# MySens-easyESP32-011.net
KiCad netlist of a schematic drawn in EAGLE
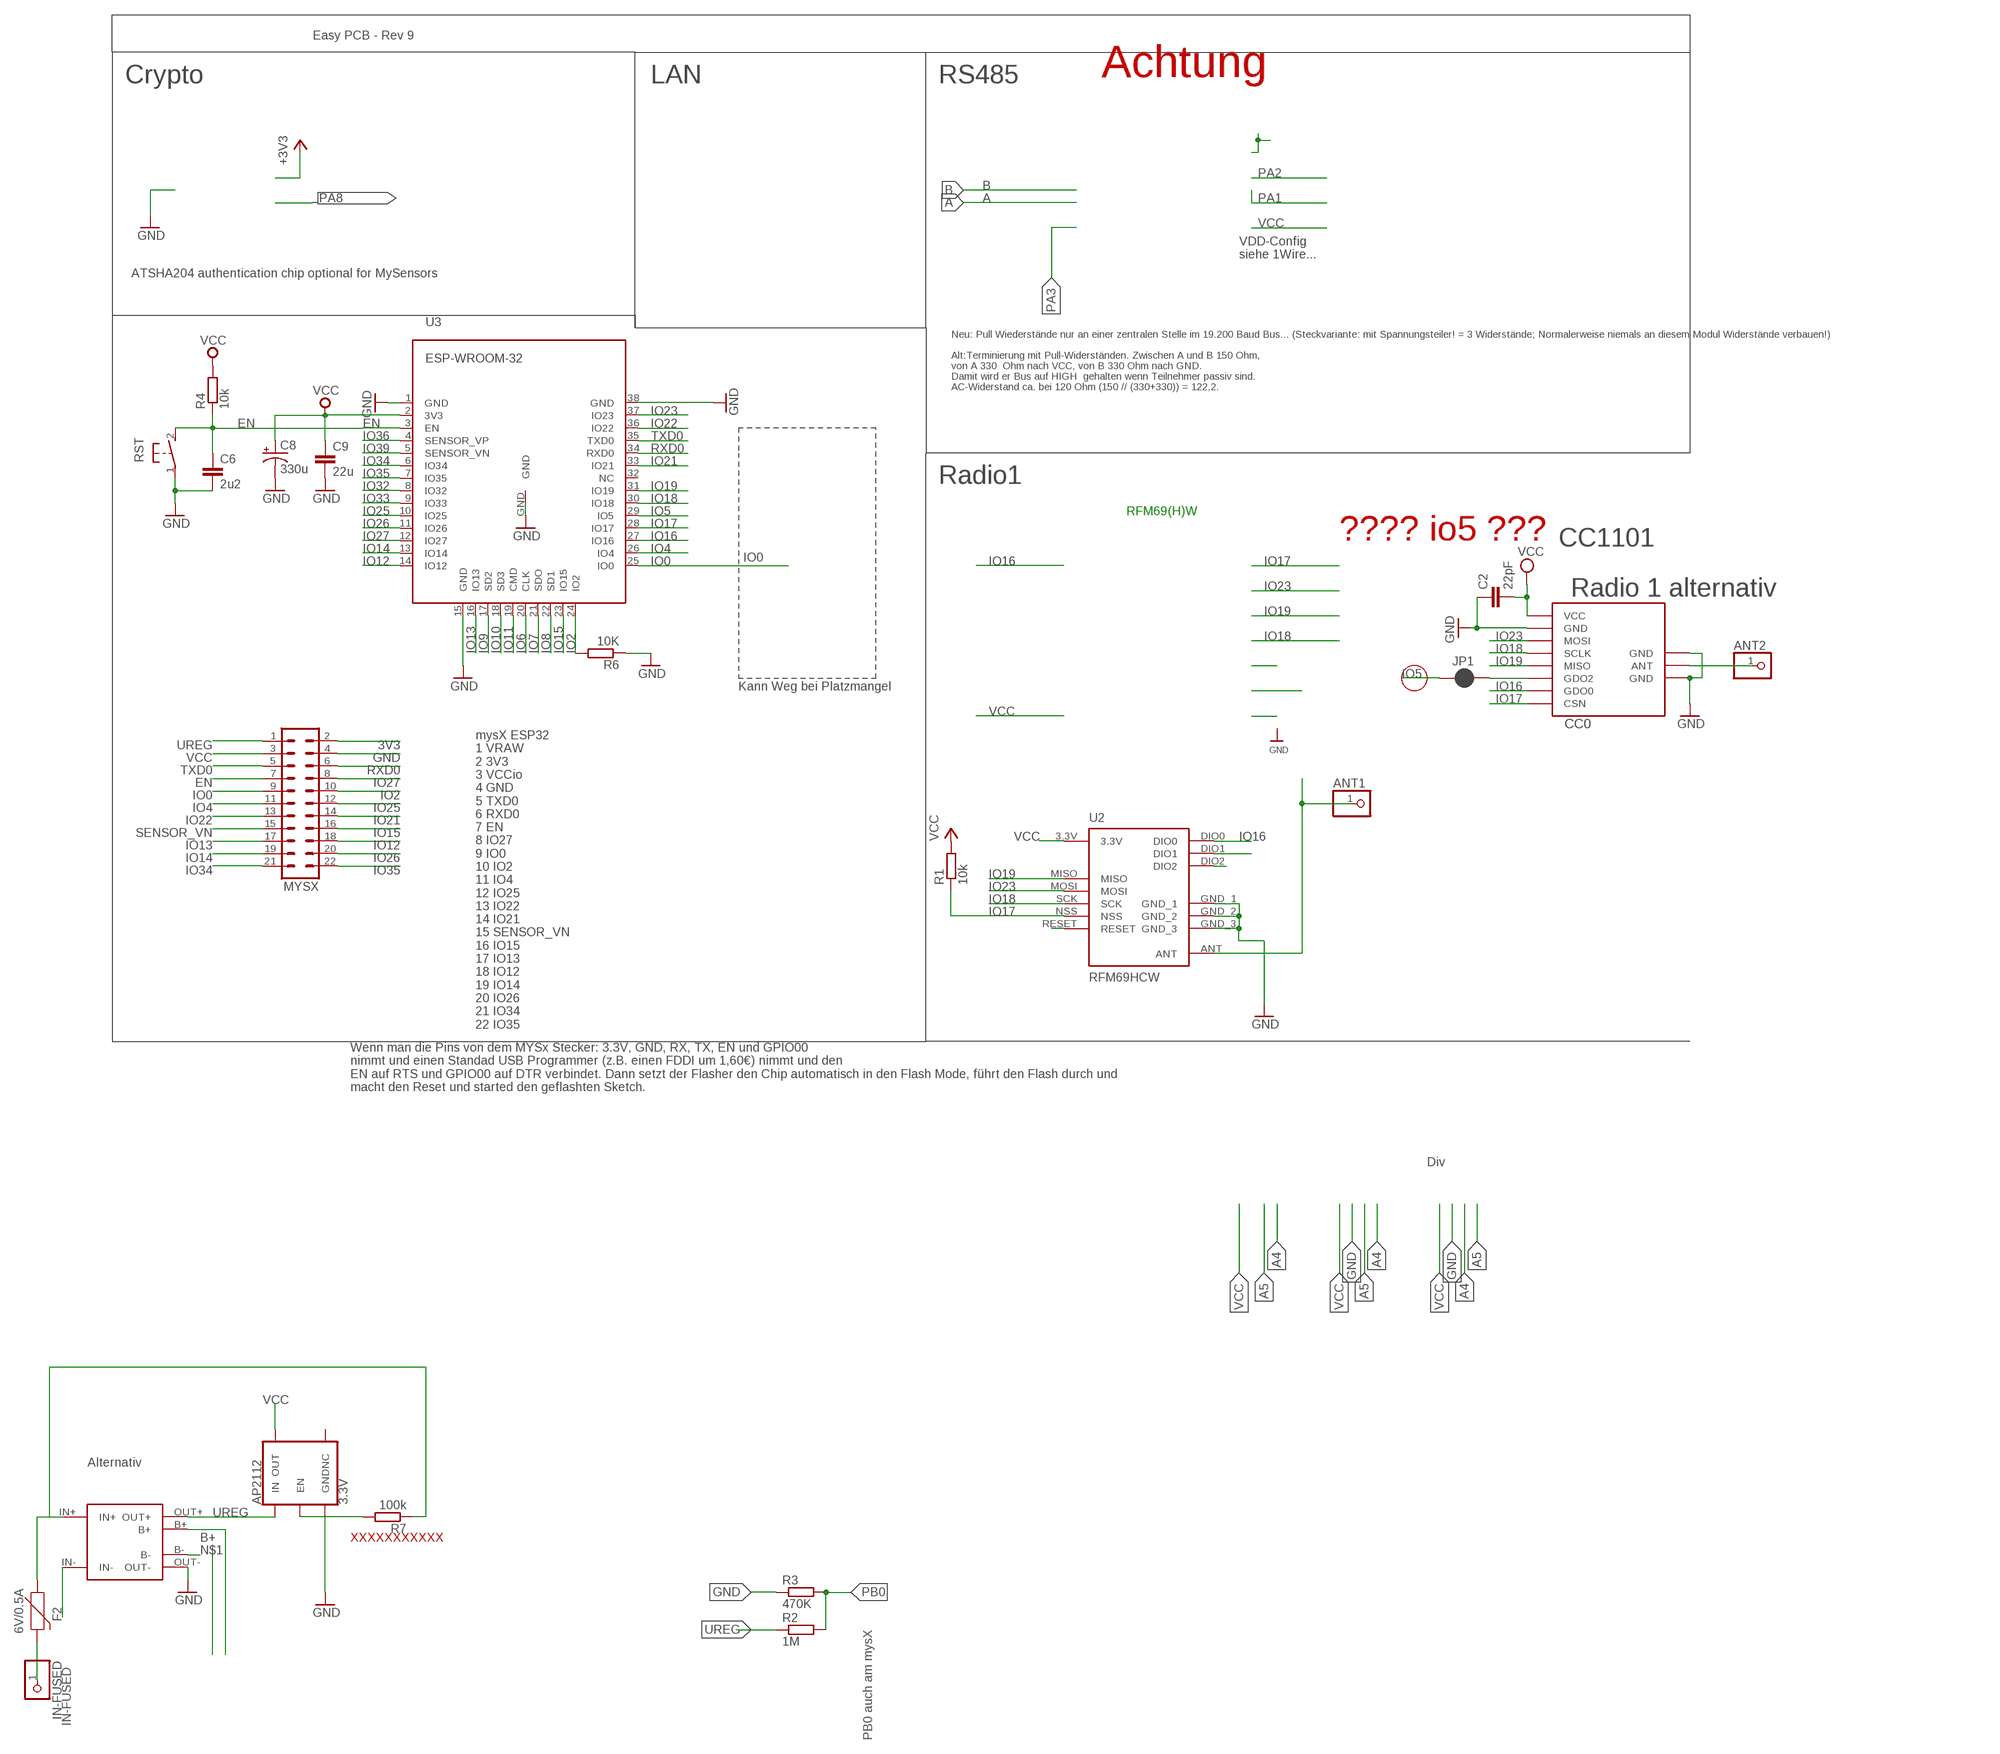
[diagram p0: schematic, sheet 1]

(export (version "E")
  (design (tool "Eeschema 10.0.6"))
  (components
    (comp (ref "ANT1")
      (value "PINHD-1X1")
      (footprint "eagle-import:1X01")
      (libsource (lib "eagle-import") (part "PINHD-1X1"))
    )
    (comp (ref "ANT2")
      (value "PINHD-1X1")
      (footprint "eagle-import:1X01")
      (libsource (lib "eagle-import") (part "PINHD-1X1"))
    )
    (comp (ref "AP2112")
      (value "3.3V")
      (footprint "eagle-import:SOT23-5")
      (libsource (lib "eagle-import") (part "V_REG_AP2112K-3.3V"))
    )
    (comp (ref "C2")
      (value "22pF")
      (footprint "eagle-import:C0805")
      (libsource (lib "eagle-import") (part "C-EUC0805"))
    )
    (comp (ref "C6")
      (value "2u2")
      (footprint "eagle-import:C0805")
      (libsource (lib "eagle-import") (part "rcl@1_C-EUC0805"))
    )
    (comp (ref "C8")
      (value "330u")
      (footprint "eagle-import:VISHAY_C")
      (libsource (lib "eagle-import") (part "CAP_POLSMD"))
    )
    (comp (ref "C9")
      (value "22u")
      (footprint "eagle-import:C0805")
      (libsource (lib "eagle-import") (part "rcl@1_C-EUC0805"))
    )
    (comp (ref "CC0")
      (value "CC1101")
      (footprint "eagle-import:CC1101_MODULE1_SMD")
      (libsource (lib "eagle-import") (part "CC1101_MODULE1SMD"))
    )
    (comp (ref "F2")
      (value "6V/0.5A")
      (footprint "eagle-import:1206")
      (libsource (lib "eagle-import") (part "PPTC_HALF-AMP"))
    )
    (comp (ref "IN-FUSED")
      (value "PINHD-1X1")
      (footprint "eagle-import:1X01")
      (libsource (lib "eagle-import") (part "PINHD-1X1"))
    )
    (comp (ref "JP1")
      (value "JUMPER-SMT_2_NC_PASTE_NO-SILK")
      (footprint "eagle-import:SMT-JUMPER_2_NC_PASTE_NO-SILK")
      (libsource (lib "eagle-import") (part "JUMPER-SMT_2_NC_PASTE_NO-SILK"))
    )
    (comp (ref "MYSX")
      (value "MA11-2")
      (footprint "eagle-import:MA11-2")
      (libsource (lib "eagle-import") (part "MA11-2"))
    )
    (comp (ref "R1")
      (value "10k")
      (footprint "eagle-import:M0805")
      (libsource (lib "eagle-import") (part "R-EU_M0805"))
    )
    (comp (ref "R2")
      (value "1M")
      (footprint "eagle-import:M0805")
      (libsource (lib "eagle-import") (part "R-EU_M0805"))
    )
    (comp (ref "R3")
      (value "470K")
      (footprint "eagle-import:M0805")
      (libsource (lib "eagle-import") (part "R-EU_M0805"))
    )
    (comp (ref "R4")
      (value "10k")
      (footprint "eagle-import:M0805")
      (libsource (lib "eagle-import") (part "rcl@1_R-EU_M0805"))
    )
    (comp (ref "R6")
      (value "10K")
      (footprint "eagle-import:M0805")
      (libsource (lib "eagle-import") (part "R-EU_M0805"))
    )
    (comp (ref "R7")
      (value "100k")
      (footprint "eagle-import:M0805")
      (libsource (lib "eagle-import") (part "R-EU_M0805"))
    )
    (comp (ref "RST")
      (value "DTSM-3")
      (footprint "eagle-import:DTSM-3")
      (libsource (lib "eagle-import") (part "DTSM-3"))
    )
    (comp (ref "TP4056")
      (value "TP4056-MODULE")
      (footprint "eagle-import:TP4056-LITHIUM-PROTECTED-MODULE")
      (libsource (lib "eagle-import") (part "TP4056-MODULE"))
    )
    (comp (ref "U2")
      (value "RFM69HCW")
      (footprint "eagle-import:RFM69HCW-XXXS2")
      (libsource (lib "eagle-import") (part "RFM69HCW"))
    )
    (comp (ref "U3")
      (value "ESP-WROOM-32")
      (footprint "eagle-import:ESP-WROOM-32")
      (libsource (lib "eagle-import") (part "ESP-WROOM-32"))
    )
  )
  (nets
    (net (code "2") (name "/3V3") (class "Default")
      (node (ref "MYSX") (pin "2") (pinfunction "2_2") (pintype "passive"))
    )
    (net (code "3") (name "/B+") (class "Default")
      (node (ref "TP4056") (pin "B+") (pinfunction "B+_B+") (pintype "power_in"))
    )
    (net (code "4") (name "/EN") (class "Default")
      (node (ref "C6") (pin "1") (pinfunction "1_1") (pintype "passive"))
      (node (ref "MYSX") (pin "7") (pinfunction "7_7") (pintype "passive"))
      (node (ref "R4") (pin "1") (pinfunction "1_1") (pintype "passive"))
      (node (ref "RST") (pin "2") (pinfunction "2_2") (pintype "passive"))
      (node (ref "U3") (pin "3") (pinfunction "EN_3") (pintype "bidirectional"))
    )
    (net (code "5") (name "/IN-FUSED") (class "Default")
      (node (ref "F2") (pin "2") (pinfunction "2_2") (pintype "bidirectional"))
      (node (ref "IN-FUSED") (pin "1") (pinfunction "1_1") (pintype "passive"))
    )
    (net (code "6") (name "/IO0") (class "Default")
      (node (ref "MYSX") (pin "9") (pinfunction "9_9") (pintype "passive"))
      (node (ref "U3") (pin "25") (pinfunction "IO0_25") (pintype "bidirectional"))
    )
    (net (code "7") (name "/IO2") (class "Default")
      (node (ref "MYSX") (pin "10") (pinfunction "10_10") (pintype "passive"))
      (node (ref "R6") (pin "2") (pinfunction "2_2") (pintype "passive"))
      (node (ref "U3") (pin "24") (pinfunction "IO2_24") (pintype "bidirectional"))
    )
    (net (code "8") (name "/IO4") (class "Default")
      (node (ref "MYSX") (pin "11") (pinfunction "11_11") (pintype "passive"))
      (node (ref "U3") (pin "26") (pinfunction "IO4_26") (pintype "bidirectional"))
    )
    (net (code "9") (name "/IO5") (class "Default")
      (node (ref "JP1") (pin "1") (pinfunction "1_1") (pintype "passive"))
      (node (ref "U3") (pin "29") (pinfunction "IO5_29") (pintype "bidirectional"))
    )
    (net (code "10") (name "/IO6") (class "Default")
      (node (ref "U3") (pin "20") (pinfunction "CLK_20") (pintype "bidirectional"))
    )
    (net (code "11") (name "/IO7") (class "Default")
      (node (ref "U3") (pin "21") (pinfunction "SDO_21") (pintype "bidirectional"))
    )
    (net (code "12") (name "/IO8") (class "Default")
      (node (ref "U3") (pin "22") (pinfunction "SD1_22") (pintype "bidirectional"))
    )
    (net (code "13") (name "/IO9") (class "Default")
      (node (ref "U3") (pin "17") (pinfunction "SD2_17") (pintype "bidirectional"))
    )
    (net (code "14") (name "/IO10") (class "Default")
      (node (ref "U3") (pin "18") (pinfunction "SD3_18") (pintype "bidirectional"))
    )
    (net (code "15") (name "/IO11") (class "Default")
      (node (ref "U3") (pin "19") (pinfunction "CMD_19") (pintype "bidirectional"))
    )
    (net (code "16") (name "/IO12") (class "Default")
      (node (ref "MYSX") (pin "18") (pinfunction "18_18") (pintype "passive"))
      (node (ref "U3") (pin "14") (pinfunction "IO12_14") (pintype "bidirectional"))
    )
    (net (code "17") (name "/IO13") (class "Default")
      (node (ref "MYSX") (pin "17") (pinfunction "17_17") (pintype "passive"))
      (node (ref "U3") (pin "16") (pinfunction "IO13_16") (pintype "bidirectional"))
    )
    (net (code "18") (name "/IO14") (class "Default")
      (node (ref "MYSX") (pin "19") (pinfunction "19_19") (pintype "passive"))
      (node (ref "U3") (pin "13") (pinfunction "IO14_13") (pintype "bidirectional"))
    )
    (net (code "19") (name "/IO15") (class "Default")
      (node (ref "MYSX") (pin "16") (pinfunction "16_16") (pintype "passive"))
      (node (ref "U3") (pin "23") (pinfunction "IO15_23") (pintype "bidirectional"))
    )
    (net (code "20") (name "/IO16") (class "Default")
      (node (ref "CC0") (pin "GDO0") (pinfunction "GDO0_GDO0") (pintype "bidirectional"))
      (node (ref "U2") (pin "DIO0") (pinfunction "DIO0_DIO0") (pintype "bidirectional"))
      (node (ref "U3") (pin "27") (pinfunction "IO16_27") (pintype "bidirectional"))
    )
    (net (code "21") (name "/IO17") (class "Default")
      (node (ref "CC0") (pin "CSN") (pinfunction "CSN_CSN") (pintype "bidirectional"))
      (node (ref "R1") (pin "1") (pinfunction "1_1") (pintype "passive"))
      (node (ref "U2") (pin "NSS") (pinfunction "NSS_NSS") (pintype "input"))
      (node (ref "U3") (pin "28") (pinfunction "IO17_28") (pintype "bidirectional"))
    )
    (net (code "22") (name "/IO18") (class "Default")
      (node (ref "CC0") (pin "SCLK") (pinfunction "SCLK_SCLK") (pintype "bidirectional"))
      (node (ref "U2") (pin "SCK") (pinfunction "SCK_SCK") (pintype "input"))
      (node (ref "U3") (pin "30") (pinfunction "IO18_30") (pintype "bidirectional"))
    )
    (net (code "23") (name "/IO19") (class "Default")
      (node (ref "CC0") (pin "MISO") (pinfunction "MISO_MISO") (pintype "bidirectional"))
      (node (ref "U2") (pin "MISO") (pinfunction "MISO_MISO") (pintype "bidirectional"))
      (node (ref "U3") (pin "31") (pinfunction "IO19_31") (pintype "bidirectional"))
    )
    (net (code "24") (name "/IO21") (class "Default")
      (node (ref "MYSX") (pin "14") (pinfunction "14_14") (pintype "passive"))
      (node (ref "U3") (pin "33") (pinfunction "IO21_33") (pintype "bidirectional"))
    )
    (net (code "25") (name "/IO22") (class "Default")
      (node (ref "MYSX") (pin "13") (pinfunction "13_13") (pintype "passive"))
      (node (ref "U3") (pin "36") (pinfunction "IO22_36") (pintype "bidirectional"))
    )
    (net (code "26") (name "/IO23") (class "Default")
      (node (ref "CC0") (pin "MOSI") (pinfunction "MOSI_MOSI") (pintype "bidirectional"))
      (node (ref "U2") (pin "MOSI") (pinfunction "MOSI_MOSI") (pintype "input"))
      (node (ref "U3") (pin "37") (pinfunction "IO23_37") (pintype "bidirectional"))
    )
    (net (code "27") (name "/IO25") (class "Default")
      (node (ref "MYSX") (pin "12") (pinfunction "12_12") (pintype "passive"))
      (node (ref "U3") (pin "10") (pinfunction "IO25_10") (pintype "bidirectional"))
    )
    (net (code "28") (name "/IO26") (class "Default")
      (node (ref "MYSX") (pin "20") (pinfunction "20_20") (pintype "passive"))
      (node (ref "U3") (pin "11") (pinfunction "IO26_11") (pintype "bidirectional"))
    )
    (net (code "29") (name "/IO27") (class "Default")
      (node (ref "MYSX") (pin "8") (pinfunction "8_8") (pintype "passive"))
      (node (ref "U3") (pin "12") (pinfunction "IO27_12") (pintype "bidirectional"))
    )
    (net (code "30") (name "/IO32") (class "Default")
      (node (ref "U3") (pin "8") (pinfunction "IO32_8") (pintype "bidirectional"))
    )
    (net (code "31") (name "/IO33") (class "Default")
      (node (ref "U3") (pin "9") (pinfunction "IO33_9") (pintype "bidirectional"))
    )
    (net (code "32") (name "/IO34") (class "Default")
      (node (ref "MYSX") (pin "21") (pinfunction "21_21") (pintype "passive"))
      (node (ref "U3") (pin "6") (pinfunction "IO34_6") (pintype "bidirectional"))
    )
    (net (code "33") (name "/IO35") (class "Default")
      (node (ref "MYSX") (pin "22") (pinfunction "22_22") (pintype "passive"))
      (node (ref "U3") (pin "7") (pinfunction "IO35_7") (pintype "bidirectional"))
    )
    (net (code "34") (name "/IO36") (class "Default")
      (node (ref "U3") (pin "4") (pinfunction "SENSOR_VP_4") (pintype "bidirectional"))
    )
    (net (code "35") (name "/IO39") (class "Default")
      (node (ref "U3") (pin "5") (pinfunction "SENSOR_VN_5") (pintype "bidirectional"))
    )
    (net (code "36") (name "/N$1") (class "Default")
      (node (ref "TP4056") (pin "B-") (pinfunction "B-_B-") (pintype "power_in"))
    )
    (net (code "40") (name "/RXD0") (class "Default")
      (node (ref "MYSX") (pin "6") (pinfunction "6_6") (pintype "passive"))
      (node (ref "U3") (pin "34") (pinfunction "RXD0_34") (pintype "bidirectional"))
    )
    (net (code "41") (name "/SENSOR_VN") (class "Default")
      (node (ref "MYSX") (pin "15") (pinfunction "15_15") (pintype "passive"))
    )
    (net (code "42") (name "/TXD0") (class "Default")
      (node (ref "MYSX") (pin "5") (pinfunction "5_5") (pintype "passive"))
      (node (ref "U3") (pin "35") (pinfunction "TXD0_35") (pintype "bidirectional"))
    )
    (net (code "47") (name "GND") (class "Default")
      (node (ref "AP2112") (pin "2") (pinfunction "GND_2") (pintype "input"))
      (node (ref "C2") (pin "1") (pinfunction "1_1") (pintype "passive"))
      (node (ref "C6") (pin "2") (pinfunction "2_2") (pintype "passive"))
      (node (ref "C8") (pin "-") (pinfunction "-_-") (pintype "passive"))
      (node (ref "C9") (pin "2") (pinfunction "2_2") (pintype "passive"))
      (node (ref "CC0") (pin "GND@0") (pinfunction "GND_GND@0") (pintype "power_in"))
      (node (ref "CC0") (pin "GND@1") (pinfunction "GND_GND@1") (pintype "power_in"))
      (node (ref "CC0") (pin "GND@2") (pinfunction "GND_GND@2") (pintype "power_in"))
      (node (ref "MYSX") (pin "4") (pinfunction "4_4") (pintype "passive"))
      (node (ref "R3") (pin "1") (pinfunction "1_1") (pintype "passive"))
      (node (ref "R6") (pin "1") (pinfunction "1_1") (pintype "passive"))
      (node (ref "RST") (pin "1") (pinfunction "1_1") (pintype "passive"))
      (node (ref "TP4056") (pin "OUT-") (pinfunction "OUT-_OUT-") (pintype "power_in"))
      (node (ref "U2") (pin "GND_1") (pinfunction "GND_1_GND_1") (pintype "power_in"))
      (node (ref "U2") (pin "GND_2") (pinfunction "GND_2_GND_2") (pintype "power_in"))
      (node (ref "U2") (pin "GND_3") (pinfunction "GND_3_GND_3") (pintype "power_in"))
      (node (ref "U3") (pin "1") (pinfunction "GND_1") (pintype "bidirectional"))
      (node (ref "U3") (pin "15") (pinfunction "GND_15") (pintype "bidirectional"))
      (node (ref "U3") (pin "38") (pinfunction "GND_38") (pintype "bidirectional"))
      (node (ref "U3") (pin "GND") (pinfunction "GND_GND") (pintype "bidirectional"))
    )
    (net (code "48") (name "Net-(ANT1-Pad1)") (class "Default")
      (node (ref "ANT1") (pin "1") (pinfunction "1_1") (pintype "passive"))
      (node (ref "U2") (pin "ANT") (pinfunction "ANT_ANT") (pintype "passive"))
    )
    (net (code "49") (name "Net-(ANT2-Pad1)") (class "Default")
      (node (ref "ANT2") (pin "1") (pinfunction "1_1") (pintype "passive"))
      (node (ref "CC0") (pin "ANT") (pinfunction "ANT_ANT") (pintype "output"))
    )
    (net (code "50") (name "Net-(AP2112-EN)") (class "Default")
      (node (ref "AP2112") (pin "3") (pinfunction "EN_3") (pintype "input"))
      (node (ref "R7") (pin "2") (pinfunction "2_2") (pintype "passive"))
    )
    (net (code "51") (name "Net-(CC0-PadGDO2)") (class "Default")
      (node (ref "CC0") (pin "GDO2") (pinfunction "GDO2_GDO2") (pintype "bidirectional"))
      (node (ref "JP1") (pin "2") (pinfunction "2_2") (pintype "passive"))
    )
    (net (code "52") (name "Net-(F2-Pad1)") (class "Default")
      (node (ref "F2") (pin "1") (pinfunction "1_1") (pintype "bidirectional"))
      (node (ref "R7") (pin "1") (pinfunction "1_1") (pintype "passive"))
      (node (ref "TP4056") (pin "IN+") (pinfunction "IN+_IN+") (pintype "power_in"))
    )
    (net (code "54") (name "PB0") (class "Default")
      (node (ref "R2") (pin "2") (pinfunction "2_2") (pintype "passive"))
      (node (ref "R3") (pin "2") (pinfunction "2_2") (pintype "passive"))
    )
    (net (code "55") (name "UREG") (class "Default")
      (node (ref "AP2112") (pin "1") (pinfunction "IN_1") (pintype "input"))
      (node (ref "MYSX") (pin "1") (pinfunction "1_1") (pintype "passive"))
      (node (ref "R2") (pin "1") (pinfunction "1_1") (pintype "passive"))
      (node (ref "TP4056") (pin "OUT+") (pinfunction "OUT+_OUT+") (pintype "power_in"))
    )
    (net (code "56") (name "VCC") (class "Default")
      (node (ref "AP2112") (pin "5") (pinfunction "OUT_5") (pintype "passive"))
      (node (ref "C2") (pin "2") (pinfunction "2_2") (pintype "passive"))
      (node (ref "C8") (pin "+") (pinfunction "+_+") (pintype "passive"))
      (node (ref "C9") (pin "1") (pinfunction "1_1") (pintype "passive"))
      (node (ref "CC0") (pin "VCC") (pinfunction "VCC_VCC") (pintype "power_in"))
      (node (ref "MYSX") (pin "3") (pinfunction "3_3") (pintype "passive"))
      (node (ref "R1") (pin "2") (pinfunction "2_2") (pintype "passive"))
      (node (ref "R4") (pin "2") (pinfunction "2_2") (pintype "passive"))
      (node (ref "U2") (pin "3.3V") (pinfunction "3.3V_3.3V") (pintype "power_in"))
      (node (ref "U3") (pin "2") (pinfunction "3V3_2") (pintype "bidirectional"))
    )
    (net (code "57") (name "unconnected-(AP2112-NC-Pad4)") (class "Default")
      (node (ref "AP2112") (pin "4") (pinfunction "NC_4") (pintype "no_connect"))
    )
    (net (code "58") (name "unconnected-(TP4056-PadIN-)") (class "Default")
      (node (ref "TP4056") (pin "IN-") (pinfunction "IN-_IN-") (pintype "power_in"))
    )
    (net (code "59") (name "unconnected-(U2-PadDIO1)") (class "Default")
      (node (ref "U2") (pin "DIO1") (pinfunction "DIO1_DIO1") (pintype "bidirectional"))
    )
    (net (code "60") (name "unconnected-(U2-PadDIO2)") (class "Default")
      (node (ref "U2") (pin "DIO2") (pinfunction "DIO2_DIO2") (pintype "bidirectional"))
    )
    (net (code "61") (name "unconnected-(U2-PadRESET)") (class "Default")
      (node (ref "U2") (pin "RESET") (pinfunction "RESET_RESET") (pintype "input"))
    )
    (net (code "62") (name "unconnected-(U3-NC-Pad32)") (class "Default")
      (node (ref "U3") (pin "32") (pinfunction "NC_32") (pintype "bidirectional"))
    )
  )
)
